# Power.net
KiCad netlist of a schematic drawn in Altium Designer
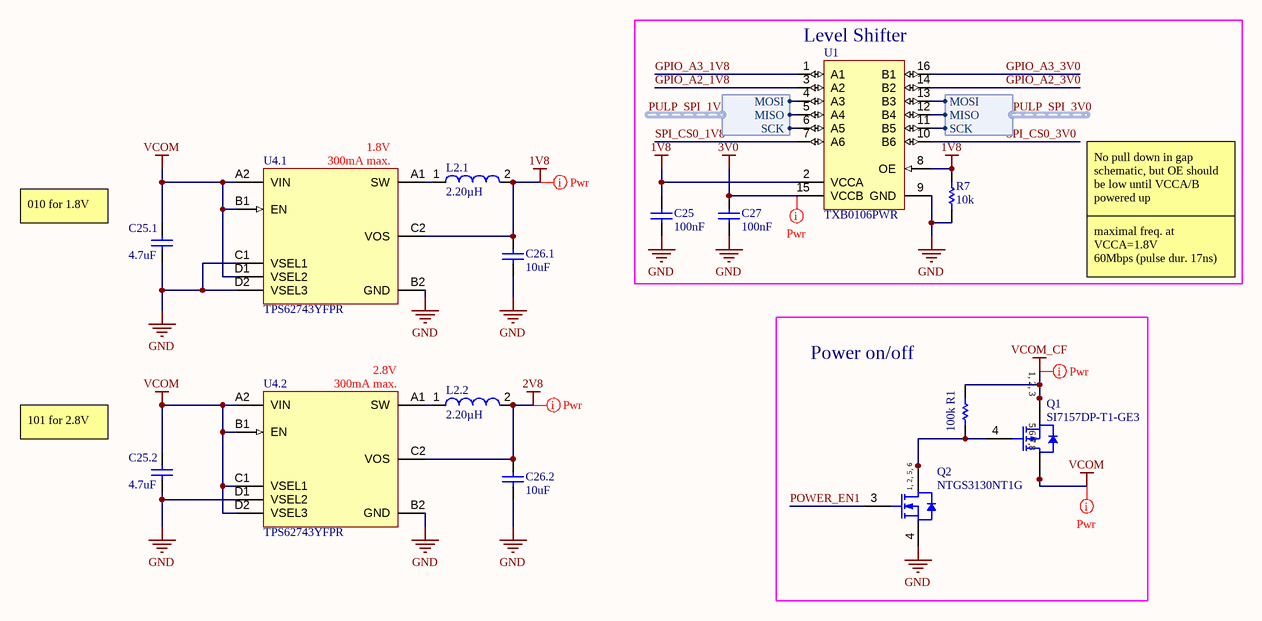
[diagram p0: Power.SchDoc]

(export (version "E")
  (design (tool "Eeschema 10.0.6"))
  (components
    (comp (ref "C25")
      (value "100nF")
      (footprint "CAPC0402(1005)60_N")
      (description "CAP 100nF 10V ±10% 0402 (1005 Metric) Thickness 0.6mm SMD")
      (fields (field (name "TOLERANCE") "Â±10%"))
      (libsource (lib "Altium Content Vault") (part "CMP-1034-02065-1"))
    )
    (comp (ref "C25.1")
      (value "4.7uF")
      (footprint "CAPC0402(1005)60_N")
      (description "CAP 4.7uF 6.3V ±20% 0402 (1005 Metric) Thickness 0.6mm SMD")
      (fields (field (name "TOLERANCE") "Â±20%"))
      (libsource (lib "Altium Content Vault") (part "CMP-1034-02137-1"))
    )
    (comp (ref "C25.2")
      (value "4.7uF")
      (footprint "CAPC0402(1005)60_N")
      (description "CAP 4.7uF 6.3V ±20% 0402 (1005 Metric) Thickness 0.6mm SMD")
      (fields (field (name "TOLERANCE") "Â±20%"))
      (libsource (lib "Altium Content Vault") (part "CMP-1034-02137-1"))
    )
    (comp (ref "C26.1")
      (value "10uF")
      (footprint "CAPC0402(1005)60_N")
      (description "CAP 10uF 6.3V ±20% 0402 (1005 Metric) Thickness 0.6mm SMD")
      (fields (field (name "TOLERANCE") "Â±20%"))
      (libsource (lib "Altium Content Vault") (part "CMP-1034-02138-1"))
    )
    (comp (ref "C26.2")
      (value "10uF")
      (footprint "CAPC0402(1005)60_N")
      (description "CAP 10uF 6.3V ±20% 0402 (1005 Metric) Thickness 0.6mm SMD")
      (fields (field (name "TOLERANCE") "Â±20%"))
      (libsource (lib "Altium Content Vault") (part "CMP-1034-02138-1"))
    )
    (comp (ref "C27")
      (value "100nF")
      (footprint "CAPC0402(1005)60_N")
      (description "CAP 100nF 10V ±10% 0402 (1005 Metric) Thickness 0.6mm SMD")
      (fields (field (name "TOLERANCE") "Â±10%"))
      (libsource (lib "Altium Content Vault") (part "CMP-1034-02065-1"))
    )
    (comp (ref "L2.1")
      (value "74479775222")
      (footprint "SMD 0805_A")
      (description "Power Multilayer Inductor WE-PMI, L=2.20 µH")
      (fields (field (name "MANUFACTURER") "Wuerth Elektronik") (field (name "INDUCTANCE") "2.20µH"))
      (libsource (lib "Altium Content Vault") (part "PAS-IND-INDUCTOR-2"))
    )
    (comp (ref "L2.2")
      (value "74479775222")
      (footprint "SMD 0805_A")
      (description "Power Multilayer Inductor WE-PMI, L=2.20 µH")
      (fields (field (name "MANUFACTURER") "Wuerth Elektronik") (field (name "INDUCTANCE") "2.20µH"))
      (libsource (lib "Altium Content Vault") (part "PAS-IND-INDUCTOR-2"))
    )
    (comp (ref "Q1")
      (value "SI7157DP-T1-GE3")
      (footprint "PowerPAK_SO-8_V")
      (description "MOSFET, P CHANNEL, -20V, -60A, POWERPAK SO-8")
      (libsource (lib "ETHZ Vault") (part "MOSFET P Channel"))
    )
    (comp (ref "Q2")
      (value "NTGS3130NT1G")
      (footprint "ONSC-TSOP-6-318G-02_V")
      (description "Power MOSFET, 20 V, 5.6 A Single, N-Channel, 6-Pin TSOP, Pb-Free, Tape and Reel")
      (fields (field (name "MANUFACTURER") "On Semiconductor"))
      (libsource (lib "Altium Content Vault") (part "CMP-1058-00957-1"))
    )
    (comp (ref "R1")
      (value "100k")
      (footprint "RESC1609X50X30NL8T20")
      (description "Chip Resistor, 10 KOhm, +/- 1%, 100 mW, -55 to 155 degC, 0603 (1608 Metric), RoHS, Tape and Reel")
      (fields (field (name "MANUFACTURER") "Vishay Semiconductor"))
      (libsource (lib "Altium Content Vault") (part "RES-2"))
    )
    (comp (ref "R7")
      (value "10k")
      (footprint "RESC1005X40X25NL05T05")
      (description "Chip Resistor, 10 KOhm, +/- 1%, 100 mW, -55 to 155 degC, 0402 (1005 Metric), RoHS, Tape and Reel")
      (fields (field (name "MANUFACTURER") "Basic Passives") (field (name "TOLERANCE") "1%"))
      (libsource (lib "Altium Content Vault") (part "CMP-2002-00607-3"))
    )
    (comp (ref "U1")
      (value "TXB0106PWR")
      (footprint "PW0016A_L")
      (fields (field (name "MANUFACTURER") "Texas Instruments"))
      (libsource (lib "Altium Content Vault") (part "TI-TXB0106-TSSOP_PW-16"))
    )
    (comp (ref "U4.1")
      (value "TPS62743YFPR")
      (footprint "YFP0008AAAA")
      (description "Buck Switching Regulator IC Positive Programmable 1.2V 1 Output 300mA 8-XFBGA, DSBGA")
      (libsource (lib "ETHZ Vault") (part "TPS62743"))
    )
    (comp (ref "U4.2")
      (value "TPS62743YFPR")
      (footprint "YFP0008AAAA")
      (description "Buck Switching Regulator IC Positive Programmable 1.2V 1 Output 300mA 8-XFBGA, DSBGA")
      (libsource (lib "ETHZ Vault") (part "TPS62743"))
    )
  )
  (nets
    (net (code "3") (name "/GPIO_A2_1V8") (class "Default")
      (node (ref "U1") (pin "3") (pinfunction "A2_3") (pintype "bidirectional"))
    )
    (net (code "4") (name "/GPIO_A2_3V0") (class "Default")
      (node (ref "U1") (pin "14") (pinfunction "B2_14") (pintype "bidirectional"))
    )
    (net (code "5") (name "/GPIO_A3_1V8") (class "Default")
      (node (ref "U1") (pin "1") (pinfunction "A1_1") (pintype "bidirectional"))
    )
    (net (code "6") (name "/GPIO_A3_3V0") (class "Default")
      (node (ref "U1") (pin "16") (pinfunction "B1_16") (pintype "bidirectional"))
    )
    (net (code "7") (name "/POWER_EN1") (class "Default")
      (node (ref "Q2") (pin "3") (pinfunction "G_3") (pintype "passive"))
    )
    (net (code "10") (name "/SPI_CS0_1V8") (class "Default")
      (node (ref "U1") (pin "7") (pinfunction "A6_7") (pintype "bidirectional"))
    )
    (net (code "11") (name "/SPI_CS0_3V0") (class "Default")
      (node (ref "U1") (pin "10") (pinfunction "B6_10") (pintype "bidirectional"))
    )
    (net (code "12") (name "1V8") (class "Default")
      (node (ref "C25") (pin "2") (pinfunction "2_2") (pintype "passive"))
      (node (ref "C26.1") (pin "2") (pinfunction "2_2") (pintype "passive"))
      (node (ref "L2.1") (pin "2") (pinfunction "2_2") (pintype "passive"))
      (node (ref "R7") (pin "2") (pinfunction "2_2") (pintype "passive"))
      (node (ref "U1") (pin "2") (pinfunction "VCCA_2") (pintype "power_in"))
      (node (ref "U1") (pin "8") (pinfunction "OE_8") (pintype "input"))
      (node (ref "U4.1") (pin "C2") (pinfunction "VOS_C2") (pintype "passive"))
    )
    (net (code "13") (name "2V8") (class "Default")
      (node (ref "C26.2") (pin "2") (pinfunction "2_2") (pintype "passive"))
      (node (ref "L2.2") (pin "2") (pinfunction "2_2") (pintype "passive"))
      (node (ref "U4.2") (pin "C2") (pinfunction "VOS_C2") (pintype "passive"))
    )
    (net (code "14") (name "3V0") (class "Default")
      (node (ref "C27") (pin "1") (pinfunction "1_1") (pintype "passive"))
      (node (ref "U1") (pin "15") (pinfunction "VCCB_15") (pintype "power_in"))
    )
    (net (code "15") (name "GND") (class "Default")
      (node (ref "C25") (pin "1") (pinfunction "1_1") (pintype "passive"))
      (node (ref "C25.1") (pin "1") (pinfunction "1_1") (pintype "passive"))
      (node (ref "C25.2") (pin "1") (pinfunction "1_1") (pintype "passive"))
      (node (ref "C26.1") (pin "1") (pinfunction "1_1") (pintype "passive"))
      (node (ref "C26.2") (pin "1") (pinfunction "1_1") (pintype "passive"))
      (node (ref "C27") (pin "2") (pinfunction "2_2") (pintype "passive"))
      (node (ref "Q2") (pin "4") (pinfunction "S_4") (pintype "passive"))
      (node (ref "R7") (pin "1") (pinfunction "1_1") (pintype "passive"))
      (node (ref "U1") (pin "9") (pinfunction "GND_9") (pintype "power_in"))
      (node (ref "U4.1") (pin "B2") (pinfunction "GND_B2") (pintype "power_in"))
      (node (ref "U4.1") (pin "C1") (pinfunction "VSEL1_C1") (pintype "passive"))
      (node (ref "U4.1") (pin "D2") (pinfunction "VSEL3_D2") (pintype "passive"))
      (node (ref "U4.2") (pin "B2") (pinfunction "GND_B2") (pintype "power_in"))
      (node (ref "U4.2") (pin "D1") (pinfunction "VSEL2_D1") (pintype "passive"))
    )
    (net (code "16") (name "Net-(Q1-G)") (class "Default")
      (node (ref "Q1") (pin "4") (pinfunction "G_4") (pintype "passive"))
      (node (ref "Q2") (pin "1") (pinfunction "D_1") (pintype "passive"))
      (node (ref "Q2") (pin "2") (pinfunction "D_2") (pintype "passive"))
      (node (ref "Q2") (pin "5") (pinfunction "D_5") (pintype "passive"))
      (node (ref "Q2") (pin "6") (pinfunction "D_6") (pintype "passive"))
      (node (ref "R1") (pin "1") (pinfunction "1_1") (pintype "passive"))
    )
    (net (code "17") (name "Net-(U4.1-SW)") (class "Default")
      (node (ref "L2.1") (pin "1") (pinfunction "1_1") (pintype "passive"))
      (node (ref "U4.1") (pin "A1") (pinfunction "SW_A1") (pintype "power_in"))
    )
    (net (code "18") (name "Net-(U4.2-SW)") (class "Default")
      (node (ref "L2.2") (pin "1") (pinfunction "1_1") (pintype "passive"))
      (node (ref "U4.2") (pin "A1") (pinfunction "SW_A1") (pintype "power_in"))
    )
    (net (code "19") (name "VCOM") (class "Default")
      (node (ref "C25.1") (pin "2") (pinfunction "2_2") (pintype "passive"))
      (node (ref "C25.2") (pin "2") (pinfunction "2_2") (pintype "passive"))
      (node (ref "Q1") (pin "5") (pinfunction "D_5") (pintype "passive"))
      (node (ref "Q1") (pin "6") (pinfunction "D_6") (pintype "passive"))
      (node (ref "Q1") (pin "7") (pinfunction "D_7") (pintype "passive"))
      (node (ref "Q1") (pin "8") (pinfunction "D_8") (pintype "passive"))
      (node (ref "U4.1") (pin "A2") (pinfunction "VIN_A2") (pintype "power_in"))
      (node (ref "U4.1") (pin "B1") (pinfunction "EN_B1") (pintype "input"))
      (node (ref "U4.1") (pin "D1") (pinfunction "VSEL2_D1") (pintype "passive"))
      (node (ref "U4.2") (pin "A2") (pinfunction "VIN_A2") (pintype "power_in"))
      (node (ref "U4.2") (pin "B1") (pinfunction "EN_B1") (pintype "input"))
      (node (ref "U4.2") (pin "C1") (pinfunction "VSEL1_C1") (pintype "passive"))
      (node (ref "U4.2") (pin "D2") (pinfunction "VSEL3_D2") (pintype "passive"))
    )
    (net (code "20") (name "VCOM_CF") (class "Default")
      (node (ref "Q1") (pin "1") (pinfunction "S_1") (pintype "passive"))
      (node (ref "Q1") (pin "2") (pinfunction "S_2") (pintype "passive"))
      (node (ref "Q1") (pin "3") (pinfunction "S_3") (pintype "passive"))
      (node (ref "R1") (pin "2") (pinfunction "2_2") (pintype "passive"))
    )
    (net (code "21") (name "unconnected-(U1-A3-Pad4)") (class "Default")
      (node (ref "U1") (pin "4") (pinfunction "A3_4") (pintype "bidirectional"))
    )
    (net (code "22") (name "unconnected-(U1-A4-Pad5)") (class "Default")
      (node (ref "U1") (pin "5") (pinfunction "A4_5") (pintype "bidirectional"))
    )
    (net (code "23") (name "unconnected-(U1-A5-Pad6)") (class "Default")
      (node (ref "U1") (pin "6") (pinfunction "A5_6") (pintype "bidirectional"))
    )
    (net (code "24") (name "unconnected-(U1-B3-Pad13)") (class "Default")
      (node (ref "U1") (pin "13") (pinfunction "B3_13") (pintype "bidirectional"))
    )
    (net (code "25") (name "unconnected-(U1-B4-Pad12)") (class "Default")
      (node (ref "U1") (pin "12") (pinfunction "B4_12") (pintype "bidirectional"))
    )
    (net (code "26") (name "unconnected-(U1-B5-Pad11)") (class "Default")
      (node (ref "U1") (pin "11") (pinfunction "B5_11") (pintype "bidirectional"))
    )
  )
)
